# murdock_mcu_v3.net
KiCad netlist of a schematic drawn in EAGLE
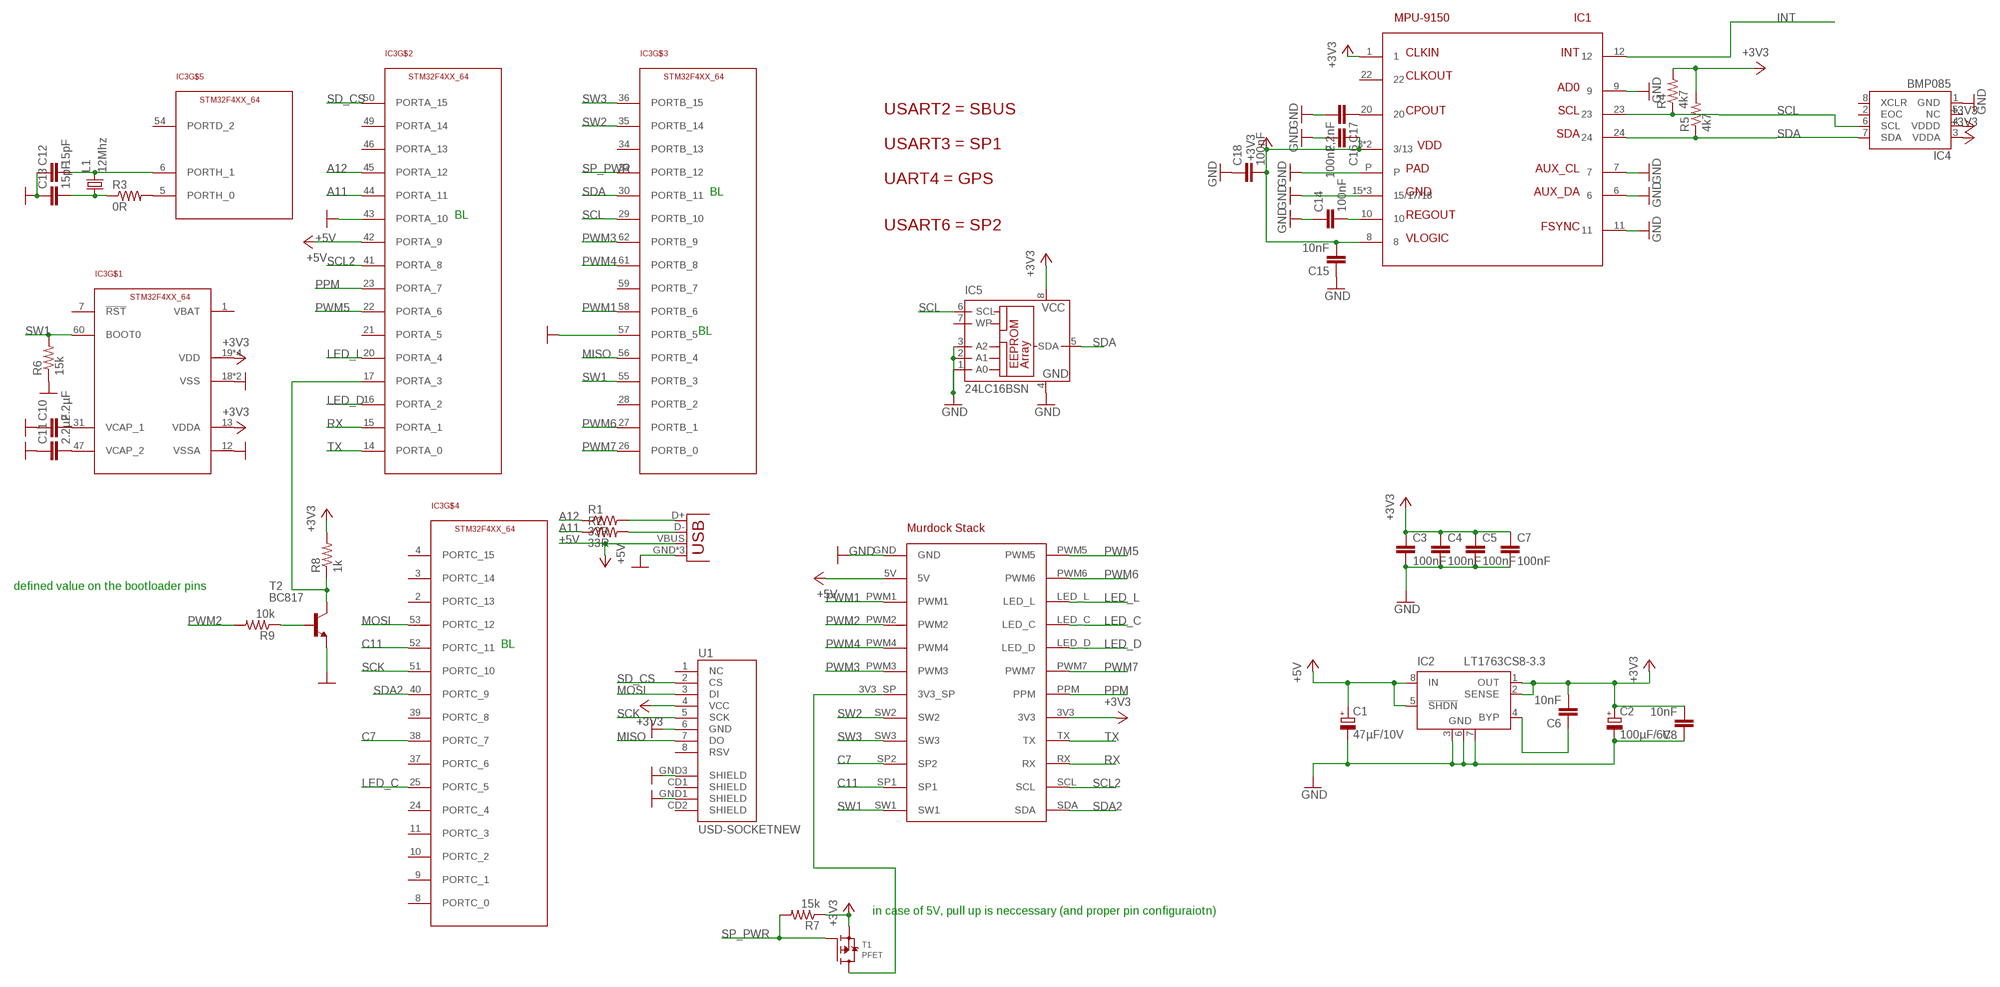
[diagram p0: schematic, sheet 1]

(export (version "E")
  (design (tool "Eeschema 10.0.6"))
  (components
    (comp (ref "C1")
      (value "47µF/10V")
      (footprint "eagle-import:SMC_C")
      (libsource (lib "eagle-import") (part "CPOL-EUSMCC"))
    )
    (comp (ref "C2")
      (value "100µF/6V")
      (footprint "eagle-import:SMC_C")
      (libsource (lib "eagle-import") (part "CPOL-EUSMCC"))
    )
    (comp (ref "C3")
      (value "100nF")
      (footprint "eagle-import:0402-CAP")
      (libsource (lib "eagle-import") (part "SparkFun-Capacitors_CAP0402-CAP"))
    )
    (comp (ref "C4")
      (value "100nF")
      (footprint "eagle-import:0402-CAP")
      (libsource (lib "eagle-import") (part "SparkFun-Capacitors_CAP0402-CAP"))
    )
    (comp (ref "C5")
      (value "100nF")
      (footprint "eagle-import:0402-CAP")
      (libsource (lib "eagle-import") (part "SparkFun-Capacitors_CAP0402-CAP"))
    )
    (comp (ref "C6")
      (value "10nF")
      (footprint "eagle-import:C0402")
      (libsource (lib "eagle-import") (part "C-EUC0402"))
    )
    (comp (ref "C7")
      (value "100nF")
      (footprint "eagle-import:0402-CAP")
      (libsource (lib "eagle-import") (part "SparkFun-Capacitors_CAP0402-CAP"))
    )
    (comp (ref "C8")
      (value "10nF")
      (footprint "eagle-import:C0402")
      (libsource (lib "eagle-import") (part "C-EUC0402"))
    )
    (comp (ref "C10")
      (value "2.2µF")
      (footprint "eagle-import:0805")
      (libsource (lib "eagle-import") (part "SparkFun-Capacitors_CAP0805"))
    )
    (comp (ref "C11")
      (value "2.2µF")
      (footprint "eagle-import:0805")
      (libsource (lib "eagle-import") (part "SparkFun-Capacitors_CAP0805"))
    )
    (comp (ref "C12")
      (value "15pF")
      (footprint "eagle-import:0402-CAP")
      (libsource (lib "eagle-import") (part "SparkFun-Capacitors_CAP0402-CAP"))
    )
    (comp (ref "C13")
      (value "15pF")
      (footprint "eagle-import:0402-CAP")
      (libsource (lib "eagle-import") (part "SparkFun-Capacitors_CAP0402-CAP"))
    )
    (comp (ref "C14")
      (value "100nF")
      (footprint "eagle-import:0402-CAP")
      (libsource (lib "eagle-import") (part "CAP0402-CAP"))
    )
    (comp (ref "C15")
      (value "10nF")
      (footprint "eagle-import:0402-CAP")
      (libsource (lib "eagle-import") (part "CAP0402-CAP"))
    )
    (comp (ref "C16")
      (value "100nF")
      (footprint "eagle-import:0402-CAP")
      (libsource (lib "eagle-import") (part "CAP0402-CAP"))
    )
    (comp (ref "C17")
      (value "2,2nF")
      (footprint "eagle-import:0402-CAP")
      (libsource (lib "eagle-import") (part "CAP0402-CAP"))
    )
    (comp (ref "C18")
      (value "100nF")
      (footprint "eagle-import:0402-CAP")
      (libsource (lib "eagle-import") (part "CAP0402-CAP"))
    )
    (comp (ref "IC1")
      (value "MPU-9150")
      (footprint "eagle-import:QFN24")
      (libsource (lib "eagle-import") (part "MPU-9150"))
    )
    (comp (ref "IC2")
      (value "LT1763CS8-3.3")
      (footprint "eagle-import:SOIC8")
      (libsource (lib "eagle-import") (part "LT1763CS8-3.3"))
    )
    (comp (ref "IC3")
      (value "STM32F4XX_64")
      (footprint "eagle-import:TQFP64")
      (libsource (lib "eagle-import") (part "STM32F4XX_64"))
    )
    (comp (ref "IC4")
      (value "BMP085")
      (footprint "eagle-import:BMP085")
      (libsource (lib "eagle-import") (part "BMP085"))
    )
    (comp (ref "IC5")
      (value "24LC16BSN")
      (footprint "eagle-import:SO-08")
      (fields (field (name "MF") "MICROCHIP") (field (name "MPN") "24LC16B/SN"))
      (libsource (lib "eagle-import") (part "24SNLC16B"))
    )
    (comp (ref "JP1")
      (value "USB-MICROB")
      (footprint "eagle-import:USB-MICROB")
      (libsource (lib "eagle-import") (part "USB-MICROB"))
    )
    (comp (ref "L1")
      (value "12Mhz")
      (footprint "eagle-import:X22")
      (libsource (lib "eagle-import") (part "X22-OSCILLATOR"))
    )
    (comp (ref "R1")
      (value "33R")
      (footprint "eagle-import:0402-RES")
      (libsource (lib "eagle-import") (part "SparkFun-Resistors_RESISTOR0402-RES"))
    )
    (comp (ref "R2")
      (value "33R")
      (footprint "eagle-import:0402-RES")
      (libsource (lib "eagle-import") (part "SparkFun-Resistors_RESISTOR0402-RES"))
    )
    (comp (ref "R3")
      (value "0R")
      (footprint "eagle-import:0402-RES")
      (libsource (lib "eagle-import") (part "SparkFun-Resistors_RESISTOR0402-RES"))
    )
    (comp (ref "R4")
      (value "4k7")
      (footprint "eagle-import:0402-RES")
      (libsource (lib "eagle-import") (part "RESISTOR0402-RES"))
    )
    (comp (ref "R5")
      (value "4k7")
      (footprint "eagle-import:0402-RES")
      (libsource (lib "eagle-import") (part "RESISTOR0402-RES"))
    )
    (comp (ref "R6")
      (value "15k")
      (footprint "eagle-import:0402-RES")
      (libsource (lib "eagle-import") (part "RESISTOR0402-RES"))
    )
    (comp (ref "R7")
      (value "15k")
      (footprint "eagle-import:0402-RES")
      (libsource (lib "eagle-import") (part "SparkFun-Resistors_RESISTOR0402-RES"))
    )
    (comp (ref "R8")
      (value "1k")
      (footprint "eagle-import:0402-RES")
      (libsource (lib "eagle-import") (part "SparkFun-Resistors_RESISTOR0402-RES"))
    )
    (comp (ref "R9")
      (value "10k")
      (footprint "eagle-import:0402-RES")
      (libsource (lib "eagle-import") (part "SparkFun-Resistors_RESISTOR0402-RES"))
    )
    (comp (ref "T1")
      (value "PFET")
      (footprint "eagle-import:SOT23-R")
      (libsource (lib "eagle-import") (part "MOSFET-P"))
    )
    (comp (ref "T2")
      (value "BC817")
      (footprint "eagle-import:SOT23")
      (libsource (lib "eagle-import") (part "BC847"))
    )
    (comp (ref "U1")
      (value "USD-SOCKETNEW")
      (footprint "eagle-import:MICRO-SD-SOCKET-PP")
      (libsource (lib "eagle-import") (part "USD-SOCKETNEW"))
    )
    (comp (ref "X2")
      (value "MURDOCK_STACK")
      (footprint "eagle-import:MURDOCK_STACK")
      (libsource (lib "eagle-import") (part "MURDOCK_STACK"))
    )
  )
  (nets
    (net (code "1") (name "+3V3") (class "Default")
      (node (ref "C15") (pin "2") (pinfunction "2_2") (pintype "passive"))
      (node (ref "C16") (pin "1") (pinfunction "1_1") (pintype "passive"))
      (node (ref "C18") (pin "2") (pinfunction "2_2") (pintype "passive"))
      (node (ref "C2") (pin "+") (pinfunction "+_+") (pintype "passive"))
      (node (ref "C3") (pin "1") (pinfunction "1_1") (pintype "passive"))
      (node (ref "C4") (pin "1") (pinfunction "1_1") (pintype "passive"))
      (node (ref "C5") (pin "1") (pinfunction "1_1") (pintype "passive"))
      (node (ref "C6") (pin "2") (pinfunction "2_2") (pintype "passive"))
      (node (ref "C7") (pin "1") (pinfunction "1_1") (pintype "passive"))
      (node (ref "C8") (pin "2") (pinfunction "2_2") (pintype "passive"))
      (node (ref "IC1") (pin "1") (pinfunction "1_1") (pintype "bidirectional"))
      (node (ref "IC1") (pin "13") (pinfunction "3/13_13") (pintype "bidirectional"))
      (node (ref "IC1") (pin "3") (pinfunction "3/13_3") (pintype "bidirectional"))
      (node (ref "IC1") (pin "8") (pinfunction "8_8") (pintype "bidirectional"))
      (node (ref "IC2") (pin "1") (pinfunction "OUT_1") (pintype "passive"))
      (node (ref "IC2") (pin "2") (pinfunction "SENSE_2") (pintype "input"))
      (node (ref "IC3") (pin "13") (pinfunction "VDDA_13") (pintype "bidirectional"))
      (node (ref "IC3") (pin "19") (pinfunction "VDD_19") (pintype "bidirectional"))
      (node (ref "IC3") (pin "32") (pinfunction "VDD_32") (pintype "bidirectional"))
      (node (ref "IC3") (pin "48") (pinfunction "VDD_48") (pintype "bidirectional"))
      (node (ref "IC3") (pin "64") (pinfunction "VDD_64") (pintype "bidirectional"))
      (node (ref "IC4") (pin "3") (pinfunction "VDDA_3") (pintype "power_in"))
      (node (ref "IC4") (pin "4") (pinfunction "VDDD_4") (pintype "power_in"))
      (node (ref "IC5") (pin "8") (pinfunction "VCC_8") (pintype "power_in"))
      (node (ref "R4") (pin "2") (pinfunction "2_2") (pintype "passive"))
      (node (ref "R5") (pin "2") (pinfunction "2_2") (pintype "passive"))
      (node (ref "R7") (pin "1") (pinfunction "1_1") (pintype "passive"))
      (node (ref "R8") (pin "2") (pinfunction "2_2") (pintype "passive"))
      (node (ref "T1") (pin "2") (pinfunction "S_2") (pintype "passive"))
      (node (ref "U1") (pin "4") (pinfunction "VCC_4") (pintype "bidirectional"))
      (node (ref "X2") (pin "3V3") (pinfunction "3V3_3V3") (pintype "bidirectional"))
    )
    (net (code "2") (name "+5V") (class "Default")
      (node (ref "C1") (pin "+") (pinfunction "+_+") (pintype "passive"))
      (node (ref "IC2") (pin "5") (pinfunction "~{SHDN}_5") (pintype "input"))
      (node (ref "IC2") (pin "8") (pinfunction "IN_8") (pintype "input"))
      (node (ref "IC3") (pin "42") (pinfunction "PORTA_9_42") (pintype "bidirectional"))
      (node (ref "JP1") (pin "VBUS") (pinfunction "VBUS_VBUS") (pintype "bidirectional"))
      (node (ref "X2") (pin "5V") (pinfunction "5V_5V") (pintype "bidirectional"))
    )
    (net (code "3") (name "/A11") (class "Default")
      (node (ref "IC3") (pin "44") (pinfunction "PORTA_11_44") (pintype "bidirectional"))
      (node (ref "R2") (pin "1") (pinfunction "1_1") (pintype "passive"))
    )
    (net (code "4") (name "/A12") (class "Default")
      (node (ref "IC3") (pin "45") (pinfunction "PORTA_12_45") (pintype "bidirectional"))
      (node (ref "R1") (pin "1") (pinfunction "1_1") (pintype "passive"))
    )
    (net (code "5") (name "/C7") (class "Default")
      (node (ref "IC3") (pin "38") (pinfunction "PORTC_7_38") (pintype "bidirectional"))
      (node (ref "X2") (pin "SP2") (pinfunction "SP2_SP2") (pintype "bidirectional"))
    )
    (net (code "6") (name "/C11") (class "Default")
      (node (ref "IC3") (pin "52") (pinfunction "PORTC_11_52") (pintype "bidirectional"))
      (node (ref "X2") (pin "SP1") (pinfunction "SP1_SP1") (pintype "bidirectional"))
    )
    (net (code "7") (name "/INT") (class "Default")
      (node (ref "IC1") (pin "12") (pinfunction "12_12") (pintype "bidirectional"))
    )
    (net (code "8") (name "/LED_C") (class "Default")
      (node (ref "IC3") (pin "25") (pinfunction "PORTC_5_25") (pintype "bidirectional"))
      (node (ref "X2") (pin "LED_C") (pinfunction "LED_C_LED_C") (pintype "bidirectional"))
    )
    (net (code "9") (name "/LED_D") (class "Default")
      (node (ref "IC3") (pin "16") (pinfunction "PORTA_2_16") (pintype "bidirectional"))
      (node (ref "X2") (pin "LED_D") (pinfunction "LED_D_LED_D") (pintype "bidirectional"))
    )
    (net (code "10") (name "/LED_L") (class "Default")
      (node (ref "IC3") (pin "20") (pinfunction "PORTA_4_20") (pintype "bidirectional"))
      (node (ref "X2") (pin "LED_L") (pinfunction "LED_L_LED_L") (pintype "bidirectional"))
    )
    (net (code "11") (name "/MISO") (class "Default")
      (node (ref "IC3") (pin "56") (pinfunction "PORTB_4_56") (pintype "bidirectional"))
      (node (ref "U1") (pin "7") (pinfunction "DO_7") (pintype "bidirectional"))
    )
    (net (code "12") (name "/MOSI") (class "Default")
      (node (ref "IC3") (pin "53") (pinfunction "PORTC_12_53") (pintype "bidirectional"))
      (node (ref "U1") (pin "3") (pinfunction "DI_3") (pintype "bidirectional"))
    )
    (net (code "13") (name "/PPM") (class "Default")
      (node (ref "IC3") (pin "23") (pinfunction "PORTA_7_23") (pintype "bidirectional"))
      (node (ref "X2") (pin "PPM") (pinfunction "PPM_PPM") (pintype "bidirectional"))
    )
    (net (code "14") (name "/PWM1") (class "Default")
      (node (ref "IC3") (pin "58") (pinfunction "PORTB_6_58") (pintype "bidirectional"))
      (node (ref "X2") (pin "PWM1") (pinfunction "PWM1_PWM1") (pintype "bidirectional"))
    )
    (net (code "15") (name "/PWM2") (class "Default")
      (node (ref "R9") (pin "2") (pinfunction "2_2") (pintype "passive"))
      (node (ref "X2") (pin "PWM2") (pinfunction "PWM2_PWM2") (pintype "bidirectional"))
    )
    (net (code "16") (name "/PWM3") (class "Default")
      (node (ref "IC3") (pin "62") (pinfunction "PORTB_9_62") (pintype "bidirectional"))
      (node (ref "X2") (pin "PWM3") (pinfunction "PWM3_PWM3") (pintype "bidirectional"))
    )
    (net (code "17") (name "/PWM4") (class "Default")
      (node (ref "IC3") (pin "61") (pinfunction "PORTB_8_61") (pintype "bidirectional"))
      (node (ref "X2") (pin "PWM4") (pinfunction "PWM4_PWM4") (pintype "bidirectional"))
    )
    (net (code "18") (name "/PWM5") (class "Default")
      (node (ref "IC3") (pin "22") (pinfunction "PORTA_6_22") (pintype "bidirectional"))
      (node (ref "X2") (pin "PWM5") (pinfunction "PWM5_PWM5") (pintype "bidirectional"))
    )
    (net (code "19") (name "/PWM6") (class "Default")
      (node (ref "IC3") (pin "27") (pinfunction "PORTB_1_27") (pintype "bidirectional"))
      (node (ref "X2") (pin "PWM6") (pinfunction "PWM6_PWM6") (pintype "bidirectional"))
    )
    (net (code "20") (name "/PWM7") (class "Default")
      (node (ref "IC3") (pin "26") (pinfunction "PORTB_0_26") (pintype "bidirectional"))
      (node (ref "X2") (pin "PWM7") (pinfunction "PWM7_PWM7") (pintype "bidirectional"))
    )
    (net (code "21") (name "/RX") (class "Default")
      (node (ref "IC3") (pin "15") (pinfunction "PORTA_1_15") (pintype "bidirectional"))
      (node (ref "X2") (pin "RX") (pinfunction "RX_RX") (pintype "bidirectional"))
    )
    (net (code "22") (name "/SCK") (class "Default")
      (node (ref "IC3") (pin "51") (pinfunction "PORTC_10_51") (pintype "bidirectional"))
      (node (ref "U1") (pin "5") (pinfunction "SCK_5") (pintype "bidirectional"))
    )
    (net (code "23") (name "/SCL") (class "Default")
      (node (ref "IC1") (pin "23") (pinfunction "23_23") (pintype "bidirectional"))
      (node (ref "IC3") (pin "29") (pinfunction "PORTB_10_29") (pintype "bidirectional"))
      (node (ref "IC4") (pin "6") (pinfunction "SCL_6") (pintype "input"))
      (node (ref "IC5") (pin "6") (pinfunction "SCL_6") (pintype "input"))
      (node (ref "R4") (pin "1") (pinfunction "1_1") (pintype "passive"))
    )
    (net (code "24") (name "/SCL2") (class "Default")
      (node (ref "IC3") (pin "41") (pinfunction "PORTA_8_41") (pintype "bidirectional"))
      (node (ref "X2") (pin "SCL") (pinfunction "SCL_SCL") (pintype "bidirectional"))
    )
    (net (code "25") (name "/SDA") (class "Default")
      (node (ref "IC1") (pin "24") (pinfunction "24_24") (pintype "bidirectional"))
      (node (ref "IC3") (pin "30") (pinfunction "PORTB_11_30") (pintype "bidirectional"))
      (node (ref "IC4") (pin "7") (pinfunction "SDA_7") (pintype "bidirectional"))
      (node (ref "IC5") (pin "5") (pinfunction "SDA_5") (pintype "bidirectional"))
      (node (ref "R5") (pin "1") (pinfunction "1_1") (pintype "passive"))
    )
    (net (code "26") (name "/SDA2") (class "Default")
      (node (ref "IC3") (pin "40") (pinfunction "PORTC_9_40") (pintype "bidirectional"))
      (node (ref "X2") (pin "SDA") (pinfunction "SDA_SDA") (pintype "bidirectional"))
    )
    (net (code "27") (name "/SD_CS") (class "Default")
      (node (ref "IC3") (pin "50") (pinfunction "PORTA_15_50") (pintype "bidirectional"))
      (node (ref "U1") (pin "2") (pinfunction "CS_2") (pintype "bidirectional"))
    )
    (net (code "28") (name "/SP_PWR") (class "Default")
      (node (ref "IC3") (pin "33") (pinfunction "PORTB_12_33") (pintype "bidirectional"))
      (node (ref "R7") (pin "2") (pinfunction "2_2") (pintype "passive"))
      (node (ref "T1") (pin "1") (pinfunction "G_1") (pintype "passive"))
    )
    (net (code "29") (name "/SW1") (class "Default")
      (node (ref "IC3") (pin "55") (pinfunction "PORTB_3_55") (pintype "bidirectional"))
      (node (ref "IC3") (pin "60") (pinfunction "BOOT0_60") (pintype "bidirectional"))
      (node (ref "R6") (pin "2") (pinfunction "2_2") (pintype "passive"))
      (node (ref "X2") (pin "SW1") (pinfunction "SW1_SW1") (pintype "bidirectional"))
    )
    (net (code "30") (name "/SW2") (class "Default")
      (node (ref "IC3") (pin "35") (pinfunction "PORTB_14_35") (pintype "bidirectional"))
      (node (ref "X2") (pin "SW2") (pinfunction "SW2_SW2") (pintype "bidirectional"))
    )
    (net (code "31") (name "/SW3") (class "Default")
      (node (ref "IC3") (pin "36") (pinfunction "PORTB_15_36") (pintype "bidirectional"))
      (node (ref "X2") (pin "SW3") (pinfunction "SW3_SW3") (pintype "bidirectional"))
    )
    (net (code "32") (name "/TX") (class "Default")
      (node (ref "IC3") (pin "14") (pinfunction "PORTA_0_14") (pintype "bidirectional"))
      (node (ref "X2") (pin "TX") (pinfunction "TX_TX") (pintype "bidirectional"))
    )
    (net (code "33") (name "GND") (class "Default")
      (node (ref "C1") (pin "-") (pinfunction "-_-") (pintype "passive"))
      (node (ref "C10") (pin "1") (pinfunction "1_1") (pintype "passive"))
      (node (ref "C11") (pin "1") (pinfunction "1_1") (pintype "passive"))
      (node (ref "C12") (pin "1") (pinfunction "1_1") (pintype "passive"))
      (node (ref "C13") (pin "1") (pinfunction "1_1") (pintype "passive"))
      (node (ref "C14") (pin "1") (pinfunction "1_1") (pintype "passive"))
      (node (ref "C15") (pin "1") (pinfunction "1_1") (pintype "passive"))
      (node (ref "C16") (pin "2") (pinfunction "2_2") (pintype "passive"))
      (node (ref "C17") (pin "2") (pinfunction "2_2") (pintype "passive"))
      (node (ref "C18") (pin "1") (pinfunction "1_1") (pintype "passive"))
      (node (ref "C2") (pin "-") (pinfunction "-_-") (pintype "passive"))
      (node (ref "C3") (pin "2") (pinfunction "2_2") (pintype "passive"))
      (node (ref "C4") (pin "2") (pinfunction "2_2") (pintype "passive"))
      (node (ref "C5") (pin "2") (pinfunction "2_2") (pintype "passive"))
      (node (ref "C7") (pin "2") (pinfunction "2_2") (pintype "passive"))
      (node (ref "C8") (pin "1") (pinfunction "1_1") (pintype "passive"))
      (node (ref "IC1") (pin "11") (pinfunction "11_11") (pintype "bidirectional"))
      (node (ref "IC1") (pin "15") (pinfunction "15/17/18_15") (pintype "bidirectional"))
      (node (ref "IC1") (pin "17") (pinfunction "15/17/18_17") (pintype "bidirectional"))
      (node (ref "IC1") (pin "18") (pinfunction "15/17/18_18") (pintype "bidirectional"))
      (node (ref "IC1") (pin "6") (pinfunction "6_6") (pintype "bidirectional"))
      (node (ref "IC1") (pin "7") (pinfunction "7_7") (pintype "bidirectional"))
      (node (ref "IC1") (pin "9") (pinfunction "9_9") (pintype "bidirectional"))
      (node (ref "IC1") (pin "P") (pinfunction "P_P") (pintype "bidirectional"))
      (node (ref "IC2") (pin "3") (pinfunction "GND_3") (pintype "power_in"))
      (node (ref "IC2") (pin "6") (pinfunction "GND_6") (pintype "power_in"))
      (node (ref "IC2") (pin "7") (pinfunction "GND_7") (pintype "power_in"))
      (node (ref "IC3") (pin "12") (pinfunction "VSSA_12") (pintype "bidirectional"))
      (node (ref "IC3") (pin "18") (pinfunction "VSS_18") (pintype "bidirectional"))
      (node (ref "IC3") (pin "43") (pinfunction "PORTA_10_43") (pintype "bidirectional"))
      (node (ref "IC3") (pin "57") (pinfunction "PORTB_5_57") (pintype "bidirectional"))
      (node (ref "IC3") (pin "63") (pinfunction "VSS_63") (pintype "bidirectional"))
      (node (ref "IC4") (pin "1") (pinfunction "GND_1") (pintype "power_in"))
      (node (ref "IC5") (pin "1") (pinfunction "A0_1") (pintype "input"))
      (node (ref "IC5") (pin "2") (pinfunction "A1_2") (pintype "input"))
      (node (ref "IC5") (pin "3") (pinfunction "A2_3") (pintype "input"))
      (node (ref "IC5") (pin "4") (pinfunction "GND_4") (pintype "power_in"))
      (node (ref "JP1") (pin "GND") (pinfunction "GND_GND") (pintype "bidirectional"))
      (node (ref "JP1") (pin "MT1") (pinfunction "GND_MT1") (pintype "bidirectional"))
      (node (ref "JP1") (pin "MT2") (pinfunction "GND_MT2") (pintype "bidirectional"))
      (node (ref "R6") (pin "1") (pinfunction "1_1") (pintype "passive"))
      (node (ref "T2") (pin "2") (pinfunction "E_2") (pintype "passive"))
      (node (ref "U1") (pin "6") (pinfunction "GND_6") (pintype "bidirectional"))
      (node (ref "U1") (pin "GND1") (pinfunction "SHIELD_GND1") (pintype "bidirectional"))
      (node (ref "U1") (pin "GND3") (pinfunction "SHIELD_GND3") (pintype "bidirectional"))
      (node (ref "X2") (pin "GND") (pinfunction "GND_GND") (pintype "bidirectional"))
    )
    (net (code "34") (name "Net-(C13-Pad2)") (class "Default")
      (node (ref "C13") (pin "2") (pinfunction "2_2") (pintype "passive"))
      (node (ref "L1") (pin "1") (pinfunction "1_1") (pintype "passive"))
      (node (ref "R3") (pin "1") (pinfunction "1_1") (pintype "passive"))
    )
    (net (code "35") (name "Net-(C14-Pad2)") (class "Default")
      (node (ref "C14") (pin "2") (pinfunction "2_2") (pintype "passive"))
      (node (ref "IC1") (pin "10") (pinfunction "10_10") (pintype "bidirectional"))
    )
    (net (code "36") (name "Net-(C17-Pad1)") (class "Default")
      (node (ref "C17") (pin "1") (pinfunction "1_1") (pintype "passive"))
      (node (ref "IC1") (pin "20") (pinfunction "20_20") (pintype "bidirectional"))
    )
    (net (code "37") (name "Net-(IC2-BYP)") (class "Default")
      (node (ref "C6") (pin "1") (pinfunction "1_1") (pintype "passive"))
      (node (ref "IC2") (pin "4") (pinfunction "BYP_4") (pintype "input"))
    )
    (net (code "38") (name "Net-(IC3A-VCAP_1)") (class "Default")
      (node (ref "C10") (pin "2") (pinfunction "2_2") (pintype "passive"))
      (node (ref "IC3") (pin "31") (pinfunction "VCAP_1_31") (pintype "bidirectional"))
    )
    (net (code "39") (name "Net-(IC3A-VCAP_2)") (class "Default")
      (node (ref "C11") (pin "2") (pinfunction "2_2") (pintype "passive"))
      (node (ref "IC3") (pin "47") (pinfunction "VCAP_2_47") (pintype "bidirectional"))
    )
    (net (code "40") (name "Net-(IC3B-PORTA_3)") (class "Default")
      (node (ref "IC3") (pin "17") (pinfunction "PORTA_3_17") (pintype "bidirectional"))
      (node (ref "R8") (pin "1") (pinfunction "1_1") (pintype "passive"))
      (node (ref "T2") (pin "3") (pinfunction "C_3") (pintype "passive"))
    )
    (net (code "41") (name "Net-(IC3E-PORTH_0)") (class "Default")
      (node (ref "IC3") (pin "5") (pinfunction "PORTH_0_5") (pintype "bidirectional"))
      (node (ref "R3") (pin "2") (pinfunction "2_2") (pintype "passive"))
    )
    (net (code "42") (name "Net-(IC3E-PORTH_1)") (class "Default")
      (node (ref "C12") (pin "2") (pinfunction "2_2") (pintype "passive"))
      (node (ref "IC3") (pin "6") (pinfunction "PORTH_1_6") (pintype "bidirectional"))
      (node (ref "L1") (pin "3") (pinfunction "2_3") (pintype "passive"))
    )
    (net (code "43") (name "Net-(JP1-PadD+)") (class "Default")
      (node (ref "JP1") (pin "D+") (pinfunction "D+_D+") (pintype "bidirectional"))
      (node (ref "R1") (pin "2") (pinfunction "2_2") (pintype "passive"))
    )
    (net (code "44") (name "Net-(JP1-PadD-)") (class "Default")
      (node (ref "JP1") (pin "D-") (pinfunction "D-_D-") (pintype "bidirectional"))
      (node (ref "R2") (pin "2") (pinfunction "2_2") (pintype "passive"))
    )
    (net (code "45") (name "Net-(T1-D)") (class "Default")
      (node (ref "T1") (pin "3") (pinfunction "D_3") (pintype "passive"))
      (node (ref "X2") (pin "3V3_SP") (pinfunction "3V3_SP_3V3_SP") (pintype "bidirectional"))
    )
    (net (code "46") (name "Net-(T2-B)") (class "Default")
      (node (ref "R9") (pin "1") (pinfunction "1_1") (pintype "passive"))
      (node (ref "T2") (pin "1") (pinfunction "B_1") (pintype "passive"))
    )
    (net (code "47") (name "unconnected-(IC1-Pad22)") (class "Default")
      (node (ref "IC1") (pin "22") (pinfunction "22_22") (pintype "bidirectional"))
    )
    (net (code "48") (name "unconnected-(IC3A-VBAT-Pad1)") (class "Default")
      (node (ref "IC3") (pin "1") (pinfunction "VBAT_1") (pintype "bidirectional"))
    )
    (net (code "49") (name "unconnected-(IC3A-~{RST}-Pad7)") (class "Default")
      (node (ref "IC3") (pin "7") (pinfunction "~{RST}_7") (pintype "bidirectional"))
    )
    (net (code "50") (name "unconnected-(IC3B-PORTA_5-Pad21)") (class "Default")
      (node (ref "IC3") (pin "21") (pinfunction "PORTA_5_21") (pintype "bidirectional"))
    )
    (net (code "51") (name "unconnected-(IC3B-PORTA_13-Pad46)") (class "Default")
      (node (ref "IC3") (pin "46") (pinfunction "PORTA_13_46") (pintype "bidirectional"))
    )
    (net (code "52") (name "unconnected-(IC3B-PORTA_14-Pad49)") (class "Default")
      (node (ref "IC3") (pin "49") (pinfunction "PORTA_14_49") (pintype "bidirectional"))
    )
    (net (code "53") (name "unconnected-(IC3C-PORTB_2-Pad28)") (class "Default")
      (node (ref "IC3") (pin "28") (pinfunction "PORTB_2_28") (pintype "bidirectional"))
    )
    (net (code "54") (name "unconnected-(IC3C-PORTB_7-Pad59)") (class "Default")
      (node (ref "IC3") (pin "59") (pinfunction "PORTB_7_59") (pintype "bidirectional"))
    )
    (net (code "55") (name "unconnected-(IC3C-PORTB_13-Pad34)") (class "Default")
      (node (ref "IC3") (pin "34") (pinfunction "PORTB_13_34") (pintype "bidirectional"))
    )
    (net (code "56") (name "unconnected-(IC3D-PORTC_0-Pad8)") (class "Default")
      (node (ref "IC3") (pin "8") (pinfunction "PORTC_0_8") (pintype "bidirectional"))
    )
    (net (code "57") (name "unconnected-(IC3D-PORTC_1-Pad9)") (class "Default")
      (node (ref "IC3") (pin "9") (pinfunction "PORTC_1_9") (pintype "bidirectional"))
    )
    (net (code "58") (name "unconnected-(IC3D-PORTC_2-Pad10)") (class "Default")
      (node (ref "IC3") (pin "10") (pinfunction "PORTC_2_10") (pintype "bidirectional"))
    )
    (net (code "59") (name "unconnected-(IC3D-PORTC_3-Pad11)") (class "Default")
      (node (ref "IC3") (pin "11") (pinfunction "PORTC_3_11") (pintype "bidirectional"))
    )
    (net (code "60") (name "unconnected-(IC3D-PORTC_4-Pad24)") (class "Default")
      (node (ref "IC3") (pin "24") (pinfunction "PORTC_4_24") (pintype "bidirectional"))
    )
    (net (code "61") (name "unconnected-(IC3D-PORTC_6-Pad37)") (class "Default")
      (node (ref "IC3") (pin "37") (pinfunction "PORTC_6_37") (pintype "bidirectional"))
    )
    (net (code "62") (name "unconnected-(IC3D-PORTC_8-Pad39)") (class "Default")
      (node (ref "IC3") (pin "39") (pinfunction "PORTC_8_39") (pintype "bidirectional"))
    )
    (net (code "63") (name "unconnected-(IC3D-PORTC_13-Pad2)") (class "Default")
      (node (ref "IC3") (pin "2") (pinfunction "PORTC_13_2") (pintype "bidirectional"))
    )
    (net (code "64") (name "unconnected-(IC3D-PORTC_14-Pad3)") (class "Default")
      (node (ref "IC3") (pin "3") (pinfunction "PORTC_14_3") (pintype "bidirectional"))
    )
    (net (code "65") (name "unconnected-(IC3D-PORTC_15-Pad4)") (class "Default")
      (node (ref "IC3") (pin "4") (pinfunction "PORTC_15_4") (pintype "bidirectional"))
    )
    (net (code "66") (name "unconnected-(IC3E-PORTD_2-Pad54)") (class "Default")
      (node (ref "IC3") (pin "54") (pinfunction "PORTD_2_54") (pintype "bidirectional"))
    )
    (net (code "67") (name "unconnected-(IC4-EOC-Pad2)") (class "Default")
      (node (ref "IC4") (pin "2") (pinfunction "EOC_2") (pintype "output"))
    )
    (net (code "68") (name "unconnected-(IC4-NC-Pad5)") (class "Default")
      (node (ref "IC4") (pin "5") (pinfunction "NC_5") (pintype "bidirectional"))
    )
    (net (code "69") (name "unconnected-(IC4-XCLR-Pad8)") (class "Default")
      (node (ref "IC4") (pin "8") (pinfunction "XCLR_8") (pintype "input"))
    )
    (net (code "70") (name "unconnected-(IC5-WP-Pad7)") (class "Default")
      (node (ref "IC5") (pin "7") (pinfunction "WP_7") (pintype "input"))
    )
    (net (code "71") (name "unconnected-(U1-NC-Pad1)") (class "Default")
      (node (ref "U1") (pin "1") (pinfunction "NC_1") (pintype "bidirectional"))
    )
    (net (code "72") (name "unconnected-(U1-RSV-Pad8)") (class "Default")
      (node (ref "U1") (pin "8") (pinfunction "RSV_8") (pintype "bidirectional"))
    )
    (net (code "73") (name "unconnected-(U1-SHIELD-PadCD1)") (class "Default")
      (node (ref "U1") (pin "CD1") (pinfunction "SHIELD_CD1") (pintype "bidirectional"))
    )
    (net (code "74") (name "unconnected-(U1-SHIELD-PadCD2)") (class "Default")
      (node (ref "U1") (pin "CD2") (pinfunction "SHIELD_CD2") (pintype "bidirectional"))
    )
  )
)
